# 2Axis-5_0-_-_0522.net
KiCad netlist of a schematic drawn in EasyEDA Pro
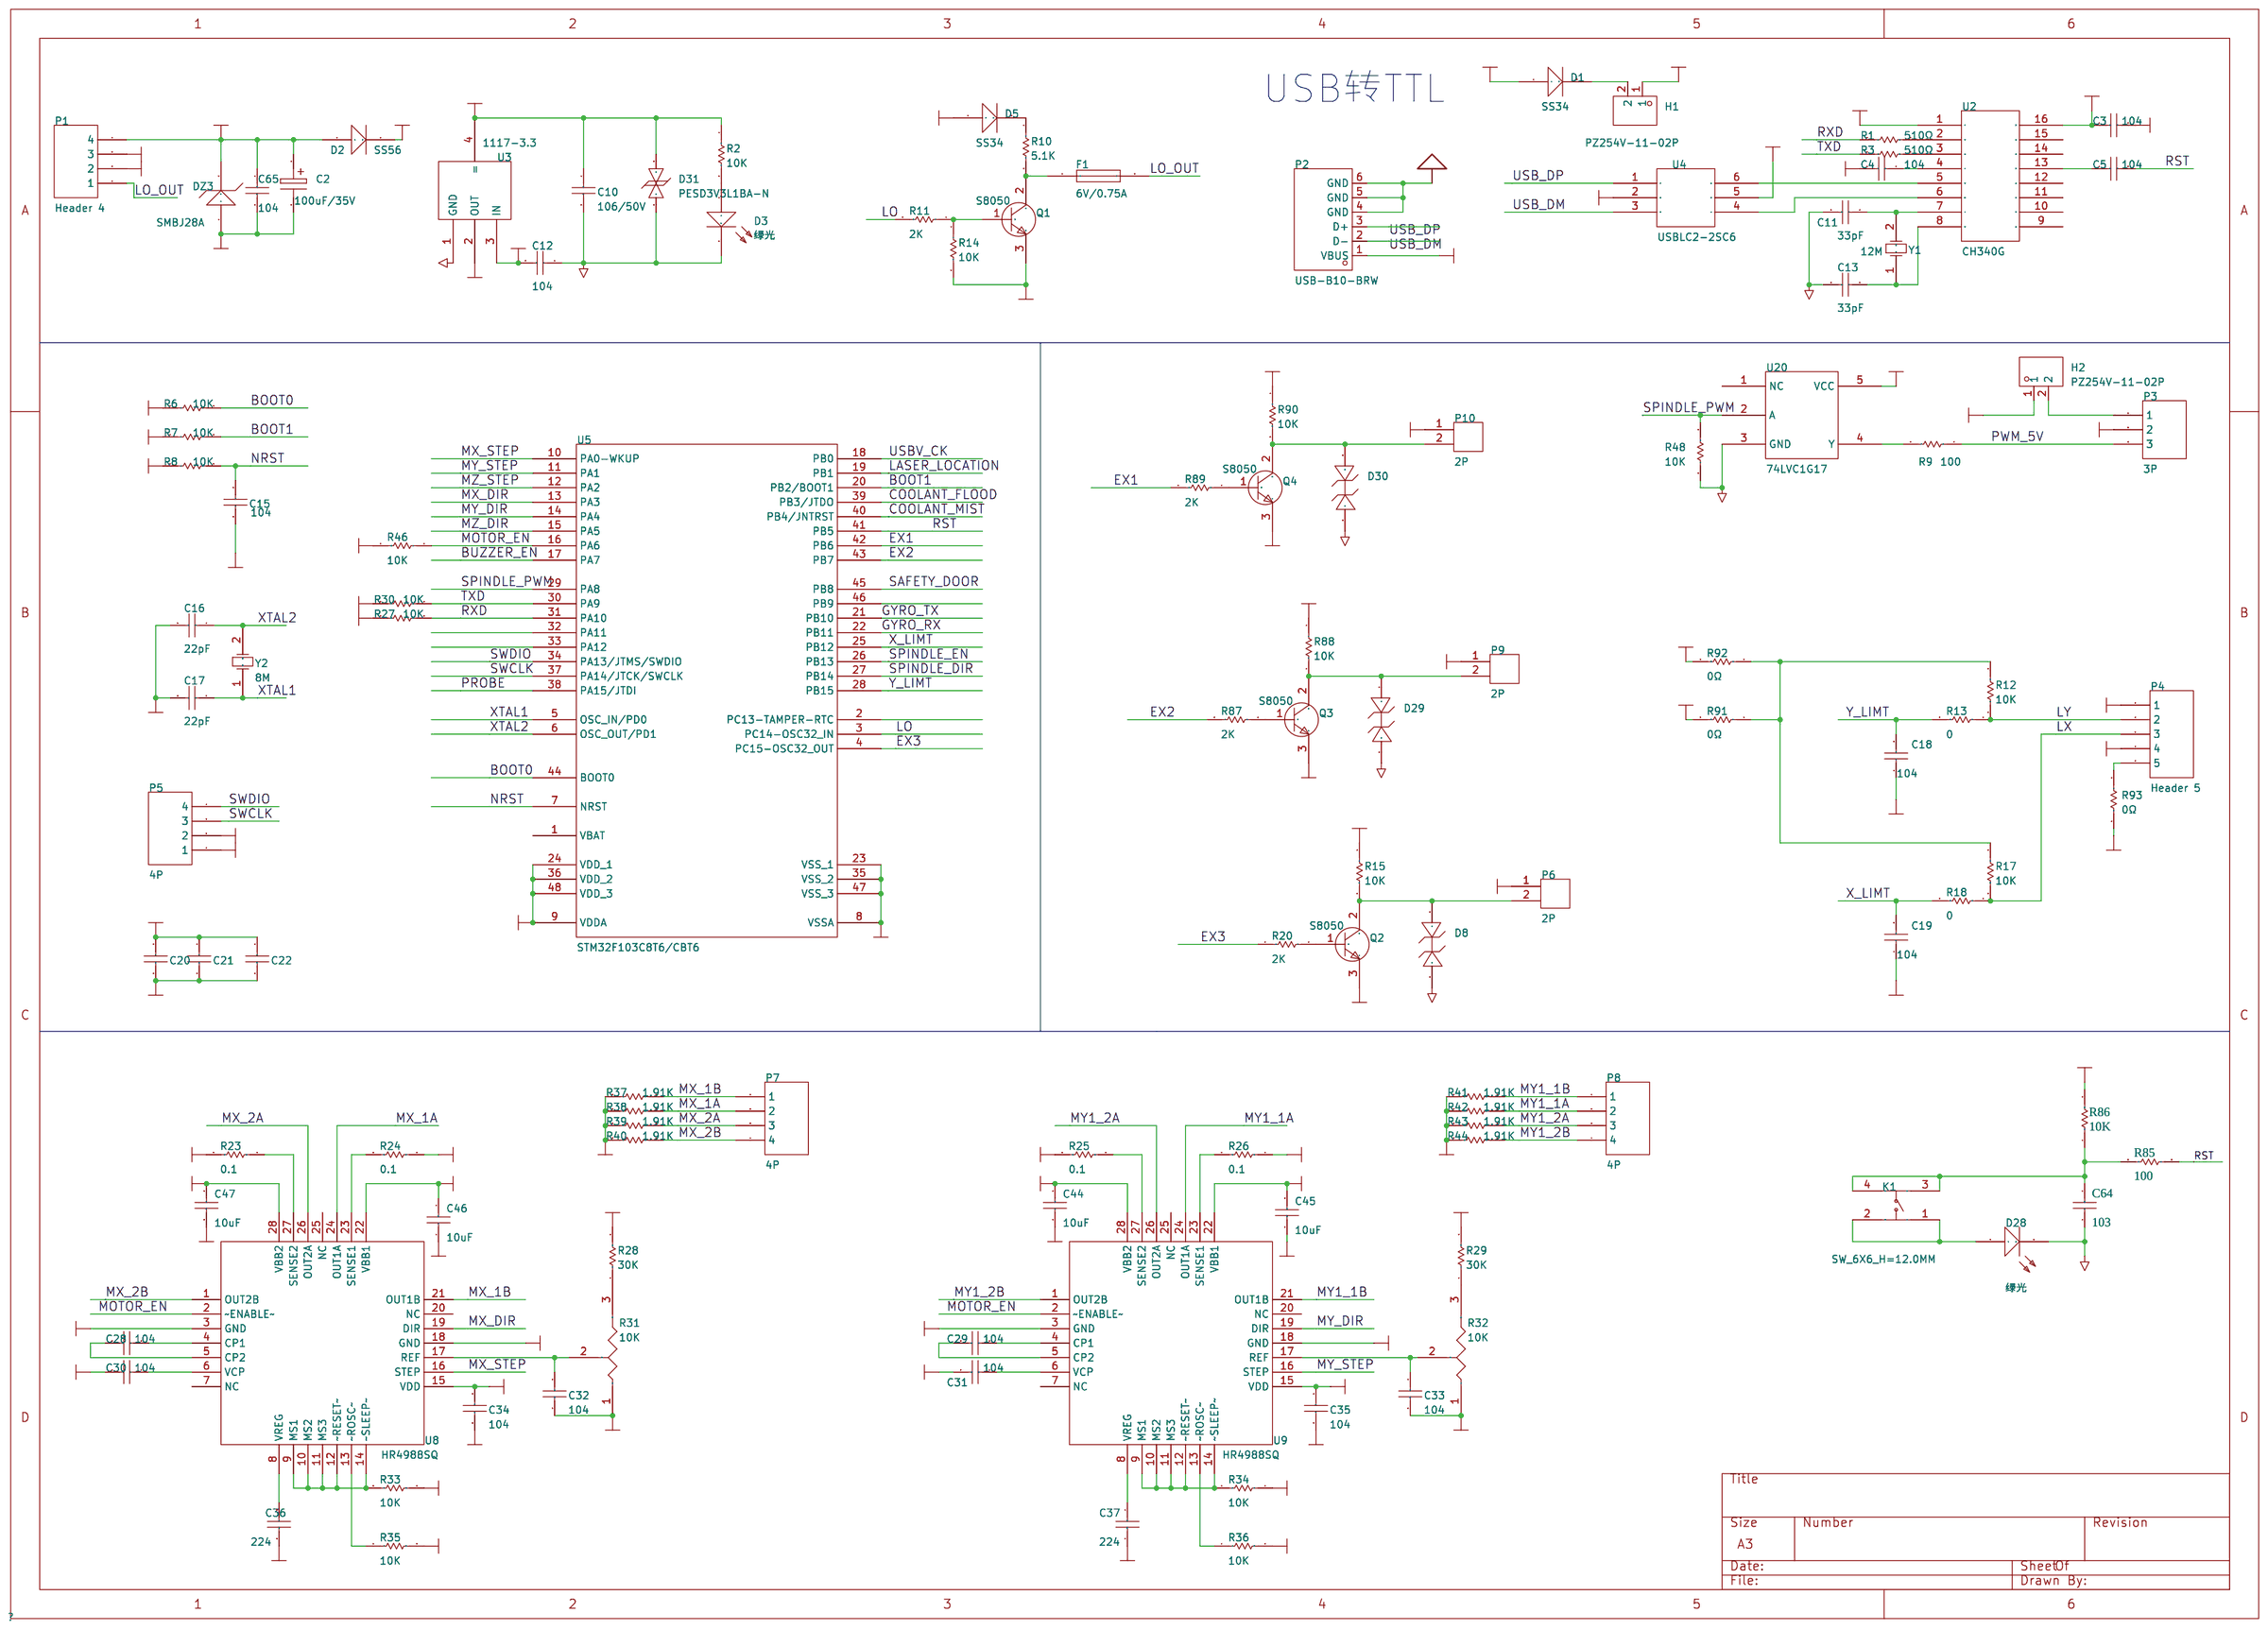
[diagram p0: 2轴南塘]
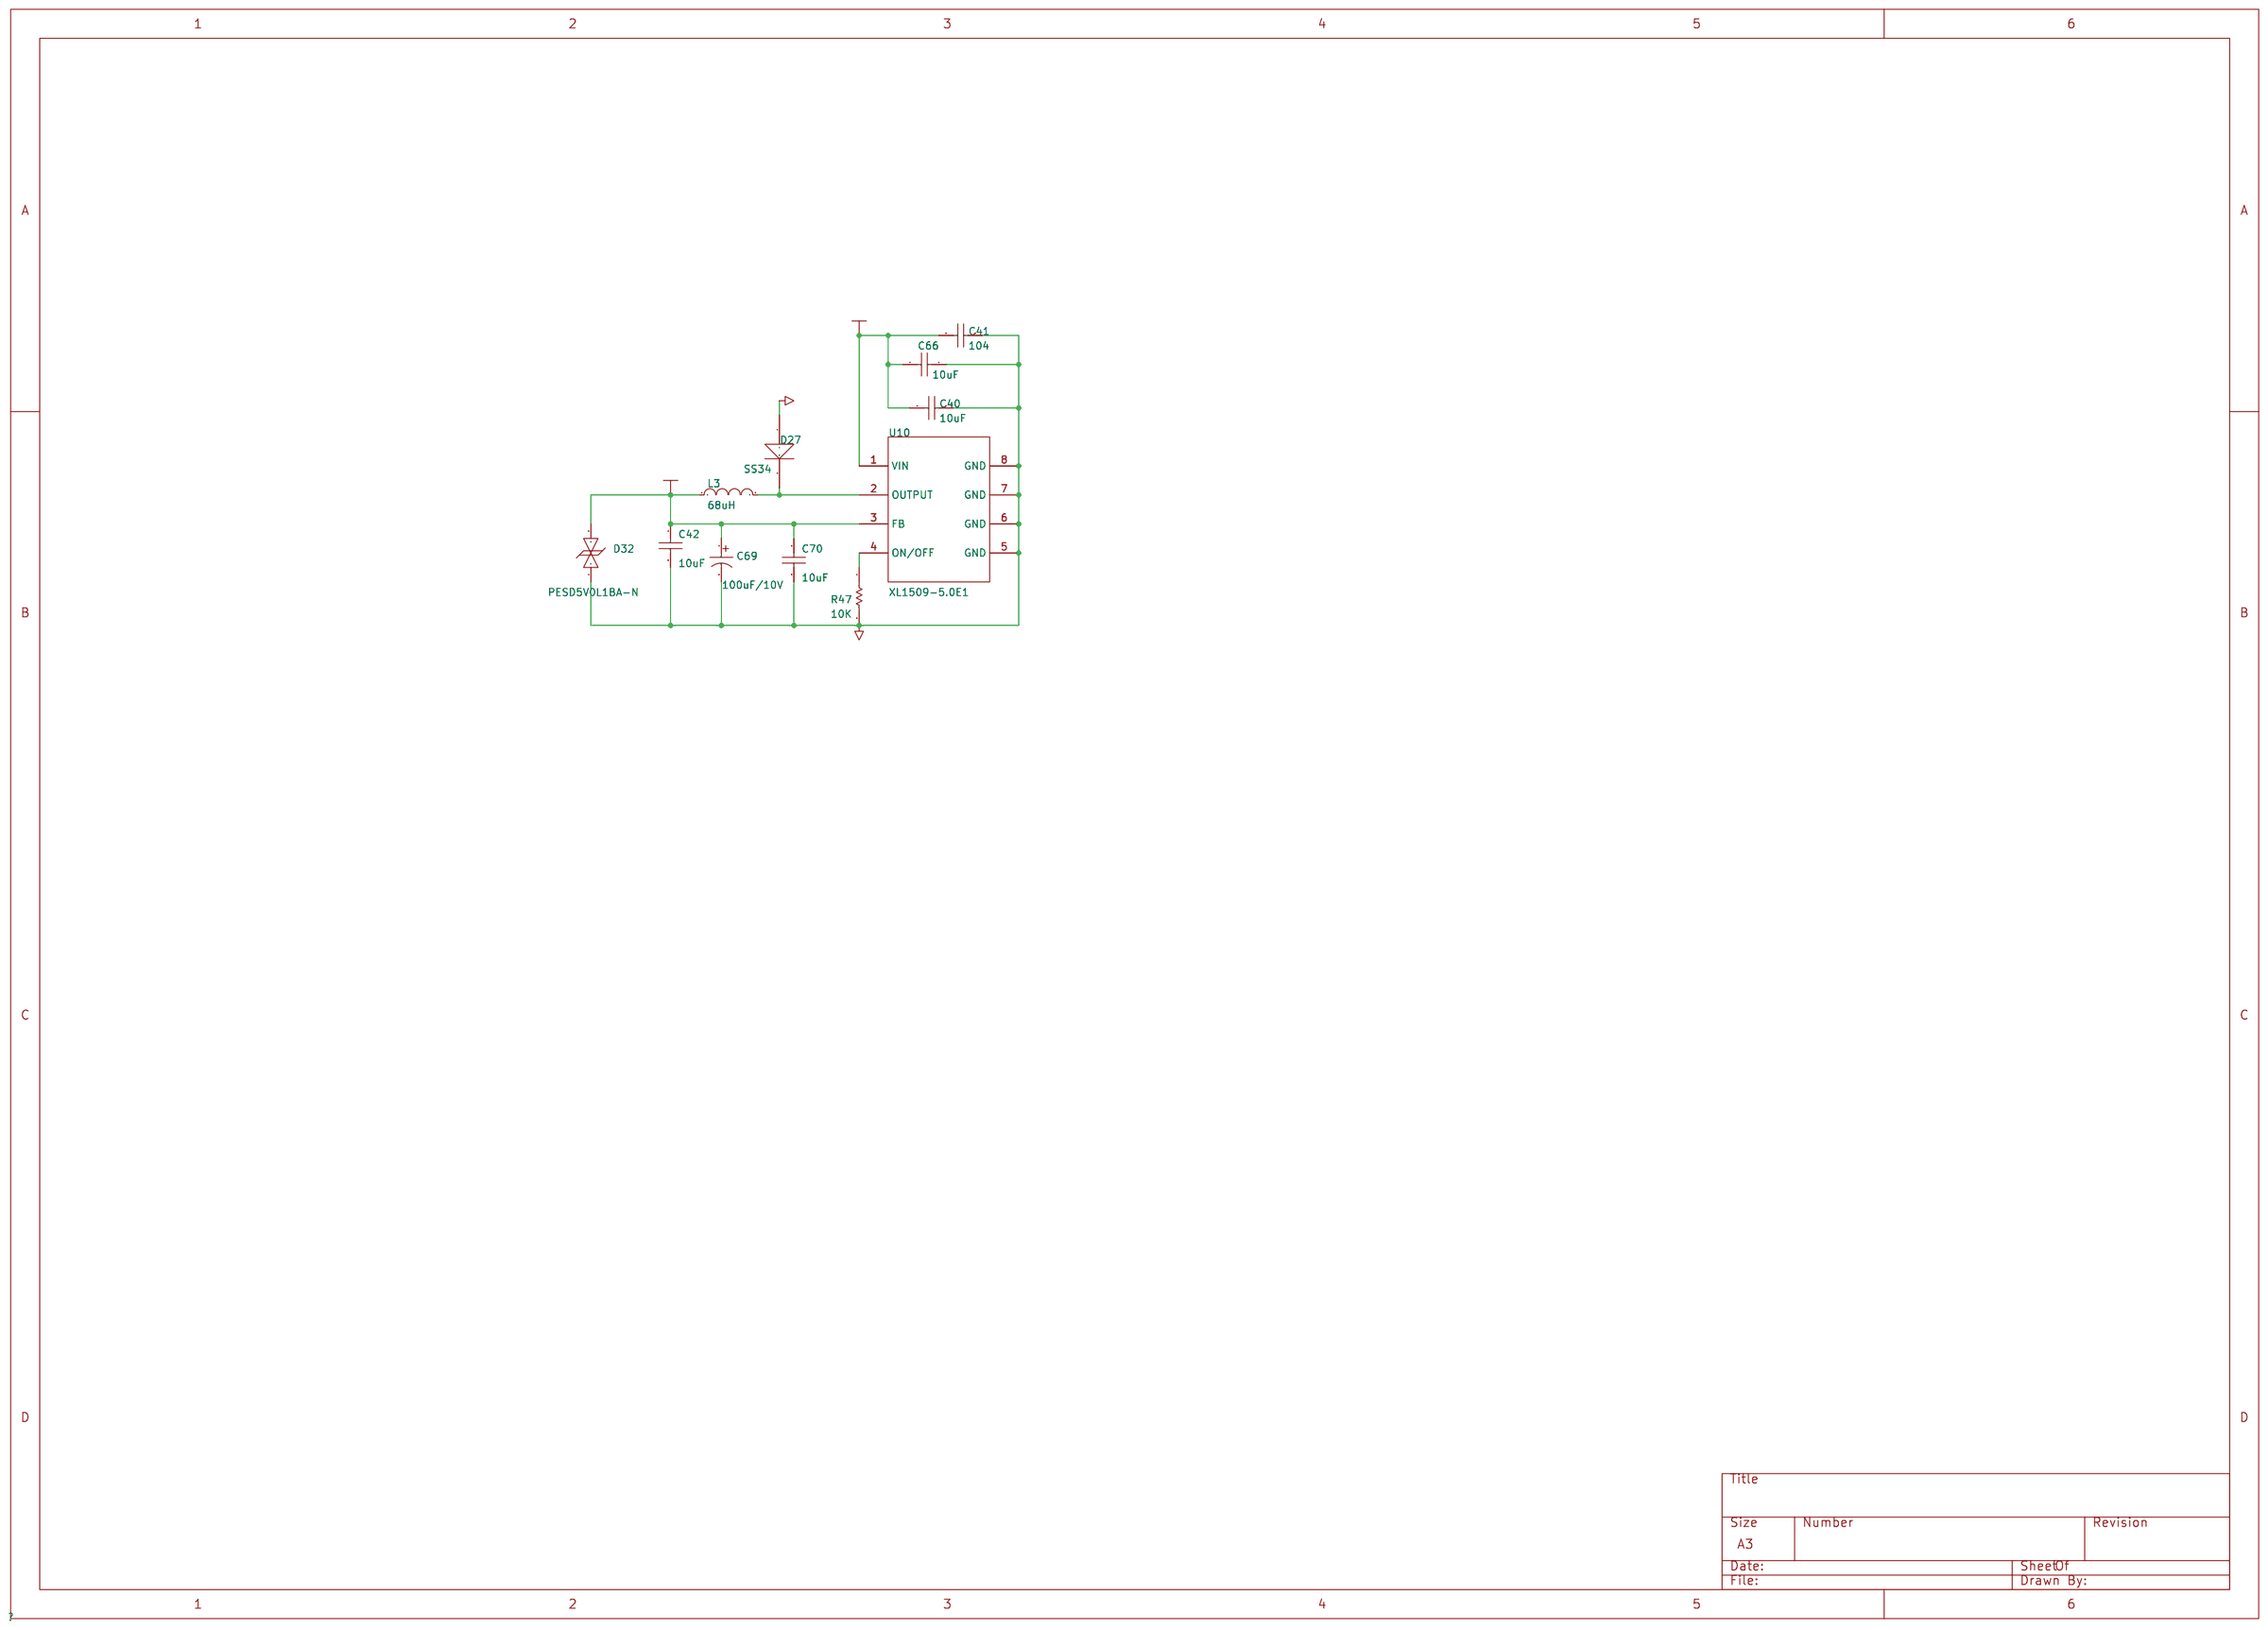
[diagram p1: 电源]

(export (version "E")
  (design (tool "Eeschema 10.0.6"))
  (components
    (comp (ref "C2")
      (value "100uF/35V")
      (footprint "easyedapro:0603C")
      (libsource (lib "easyedapro") (part "ELECTRO1"))
    )
    (comp (ref "C3")
      (value "104")
      (footprint "easyedapro:0603C")
      (description "Capacitor (Semiconductor SIM Model)")
      (libsource (lib "easyedapro") (part "Cap Semi"))
    )
    (comp (ref "C4")
      (value "104")
      (footprint "easyedapro:0603C")
      (description "Capacitor (Semiconductor SIM Model)")
      (libsource (lib "easyedapro") (part "Cap Semi"))
    )
    (comp (ref "C5")
      (value "104")
      (footprint "easyedapro:0603C")
      (description "Capacitor (Semiconductor SIM Model)")
      (libsource (lib "easyedapro") (part "Cap Semi"))
    )
    (comp (ref "C10")
      (value "106/50V")
      (footprint "easyedapro:0603C")
      (description "Capacitor (Semiconductor SIM Model)")
      (libsource (lib "easyedapro") (part "Cap Semi"))
    )
    (comp (ref "C11")
      (value "18pF")
      (footprint "easyedapro:0603C")
      (description "Capacitor (Semiconductor SIM Model)")
      (libsource (lib "easyedapro") (part "Cap Semi"))
    )
    (comp (ref "C12")
      (value "104")
      (footprint "easyedapro:0603C")
      (description "Capacitor (Semiconductor SIM Model)")
      (libsource (lib "easyedapro") (part "Cap Semi"))
    )
    (comp (ref "C13")
      (value "18pF")
      (footprint "easyedapro:0603C")
      (description "Capacitor (Semiconductor SIM Model)")
      (libsource (lib "easyedapro") (part "Cap Semi"))
    )
    (comp (ref "C15")
      (value "104")
      (footprint "easyedapro:0603C")
      (description "Capacitor (Semiconductor SIM Model)")
      (libsource (lib "easyedapro") (part "Cap Semi"))
    )
    (comp (ref "C16")
      (value "100pF")
      (footprint "easyedapro:0603C")
      (description "Capacitor (Semiconductor SIM Model)")
      (libsource (lib "easyedapro") (part "Cap Semi"))
    )
    (comp (ref "C17")
      (value "100pF")
      (footprint "easyedapro:0603C")
      (description "Capacitor (Semiconductor SIM Model)")
      (libsource (lib "easyedapro") (part "Cap Semi"))
    )
    (comp (ref "C18") (value "104") (footprint "easyedapro:0603C") (libsource (lib "") (part "CAP_1")))
    (comp (ref "C19") (value "104") (footprint "easyedapro:0603C") (libsource (lib "") (part "CAP_1")))
    (comp (ref "C20") (value "104") (footprint "easyedapro:0603C") (libsource (lib "") (part "CAP_1")))
    (comp (ref "C21") (value "104") (footprint "easyedapro:0603C") (libsource (lib "") (part "CAP_1")))
    (comp (ref "C22") (value "104") (footprint "easyedapro:0603C") (libsource (lib "") (part "CAP_1")))
    (comp (ref "C28") (value "104") (footprint "easyedapro:0603C") (libsource (lib "") (part "CAP_1")))
    (comp (ref "C29") (value "104") (footprint "easyedapro:0603C") (libsource (lib "") (part "CAP_1")))
    (comp (ref "C30") (value "104") (footprint "easyedapro:0603C") (libsource (lib "") (part "CAP_1")))
    (comp (ref "C31") (value "104") (footprint "easyedapro:0603C") (libsource (lib "") (part "CAP_1")))
    (comp (ref "C32") (value "104") (footprint "easyedapro:0603C") (libsource (lib "") (part "CAP_1")))
    (comp (ref "C33") (value "104") (footprint "easyedapro:0603C") (libsource (lib "") (part "CAP_1")))
    (comp (ref "C34") (value "104") (footprint "easyedapro:0603C") (libsource (lib "") (part "CAP_1")))
    (comp (ref "C35") (value "104") (footprint "easyedapro:0603C") (libsource (lib "") (part "CAP_1")))
    (comp (ref "C36") (value "224") (footprint "easyedapro:0603C") (libsource (lib "") (part "CAP_1")))
    (comp (ref "C37") (value "224") (footprint "easyedapro:0603C") (libsource (lib "") (part "CAP_1")))
    (comp (ref "C44") (value "10uF") (libsource (lib "easyedapro") (part "CAP")))
    (comp (ref "C45") (value "10uF") (libsource (lib "easyedapro") (part "CAP")))
    (comp (ref "C46") (value "10uF") (libsource (lib "easyedapro") (part "CAP")))
    (comp (ref "C47") (value "10uF") (libsource (lib "easyedapro") (part "CAP")))
    (comp (ref "C64") (value "103") (libsource (lib "easyedapro") (part "CAP")))
    (comp (ref "C65")
      (value "104")
      (footprint "easyedapro:0603C")
      (description "Capacitor (Semiconductor SIM Model)")
      (libsource (lib "easyedapro") (part "Cap Semi"))
    )
    (comp (ref "D1")
      (value "SS34")
      (footprint "easyedapro:SMA")
      (libsource (lib "easyedapro") (part "1N4148"))
    )
    (comp (ref "D2")
      (value "SS56")
      (footprint "easyedapro:SMA")
      (libsource (lib "easyedapro") (part "1N4148"))
    )
    (comp (ref "D3")
      (value "绿光")
      (footprint "easyedapro:0603LED")
      (libsource (lib "easyedapro") (part "LED"))
    )
    (comp (ref "D5")
      (value "SS34")
      (footprint "easyedapro:SMA")
      (libsource (lib "easyedapro") (part "1N4148"))
    )
    (comp (ref "D8")
      (value "ESD05V52D-C")
      (fields (field (name "Manufacturer") "TWGMC(台湾迪嘉)"))
      (libsource (lib "easyedapro") (part "ESD05V52D-C"))
    )
    (comp (ref "D28")
      (value "绿光")
      (footprint "easyedapro:0603LED")
      (libsource (lib "easyedapro") (part "LED"))
    )
    (comp (ref "D29")
      (value "ESD05V52D-C")
      (fields (field (name "Manufacturer") "TWGMC(台湾迪嘉)"))
      (libsource (lib "easyedapro") (part "ESD05V52D-C"))
    )
    (comp (ref "D30")
      (value "ESD05V52D-C")
      (fields (field (name "Manufacturer") "TWGMC(台湾迪嘉)"))
      (libsource (lib "easyedapro") (part "ESD05V52D-C"))
    )
    (comp (ref "D31")
      (value "PESD3V3L1BA-N")
      (footprint "easyedapro:SOD-523_L1.2-W0.8-LS1.6-BI")
      (description "极性:Bidirectional;反向关断电压（典型值）:5V (Max);击穿电压（最小值）:6V;箝位电压:15V;峰值脉冲电流（10/1000us）:5A (8/20us);")
      (fields (field (name "Manufacturer") "BORN伯恩半导体"))
      (libsource (lib "easyedapro") (part "PESD5V0S1BBN"))
    )
    (comp (ref "DZ3")
      (value "SMBJ28A")
      (footprint "easyedapro:SMA")
      (libsource (lib "easyedapro") (part "稳压二极管"))
    )
    (comp (ref "F1")
      (value "6V/0.75A")
      (footprint "easyedapro:1206R")
      (description "保险丝")
      (libsource (lib "easyedapro") (part "FUSE1"))
    )
    (comp (ref "H1")
      (value "PZ254V-11-02P")
      (footprint "easyedapro:HDR-TH_2P-P2.54-V-M")
      (fields (field (name "Manufacturer") "XFCN(兴飞)"))
      (libsource (lib "easyedapro") (part "PZ254V-11-02P"))
    )
    (comp (ref "H2")
      (value "PZ254V-11-02P")
      (footprint "easyedapro:HDR-TH_2P-P2.54-V-M")
      (fields (field (name "Manufacturer") "XFCN(兴飞)"))
      (libsource (lib "easyedapro") (part "PZ254V-11-02P"))
    )
    (comp (ref "K1")
      (value "SW_6X6_H=12.0MM")
      (footprint "easyedapro:KEY-SMD_4P-L6.0-W6.0-P4.50-LS9.0")
      (libsource (lib "easyedapro") (part "SW_6X6_H=12.0MM"))
    )
    (comp (ref "P1")
      (value "Header 4")
      (footprint "easyedapro:VH3.96-4P直插座")
      (description "Header, 4-Pin")
      (libsource (lib "easyedapro") (part "Header 4"))
    )
    (comp (ref "P2")
      (value "USB-B10-BRW")
      (footprint "easyedapro:USB-B-TH_USB-B10-BRW")
      (fields (field (name "Manufacturer") "XUNPU(讯普)"))
      (libsource (lib "easyedapro") (part "USB-B10-BRW"))
    )
    (comp (ref "P3")
      (value "3P")
      (footprint "easyedapro:HDR1X3_CON")
      (libsource (lib "easyedapro") (part "3P"))
    )
    (comp (ref "P4")
      (value "Header 5")
      (footprint "easyedapro:HDR1X5_CON")
      (description "Header, 5-Pin")
      (libsource (lib "easyedapro") (part "Header 5"))
    )
    (comp (ref "P5") (value "4P") (footprint "easyedapro:SIP4") (libsource (lib "easyedapro") (part "4P")))
    (comp (ref "P6")
      (value "2P")
      (footprint "easyedapro:HDR1X2_CON")
      (libsource (lib "easyedapro") (part "2P"))
    )
    (comp (ref "P7") (value "4P") (footprint "easyedapro:SIP4") (libsource (lib "easyedapro") (part "4P")))
    (comp (ref "P8") (value "4P") (footprint "easyedapro:SIP4") (libsource (lib "easyedapro") (part "4P")))
    (comp (ref "P9")
      (value "2P")
      (footprint "easyedapro:HDR1X2_CON")
      (libsource (lib "easyedapro") (part "2P"))
    )
    (comp (ref "P10")
      (value "2P")
      (footprint "easyedapro:HDR1X2_CON")
      (libsource (lib "easyedapro") (part "2P"))
    )
    (comp (ref "Q1")
      (value "S8050")
      (footprint "easyedapro:SOT-23")
      (libsource (lib "easyedapro") (part "NPN"))
    )
    (comp (ref "Q2")
      (value "S8050")
      (footprint "easyedapro:SOT-23")
      (libsource (lib "easyedapro") (part "NPN"))
    )
    (comp (ref "Q3")
      (value "S8050")
      (footprint "easyedapro:SOT-23")
      (libsource (lib "easyedapro") (part "NPN"))
    )
    (comp (ref "Q4")
      (value "S8050")
      (footprint "easyedapro:SOT-23")
      (libsource (lib "easyedapro") (part "NPN"))
    )
    (comp (ref "R1")
      (value "510Ω")
      (footprint "easyedapro:1206R")
      (description "Resistor")
      (libsource (lib "") (part "RES_1"))
    )
    (comp (ref "R2")
      (value "10K")
      (footprint "easyedapro:1206R")
      (description "Resistor")
      (libsource (lib "") (part "RES_1"))
    )
    (comp (ref "R3")
      (value "510Ω")
      (footprint "easyedapro:1206R")
      (description "Resistor")
      (libsource (lib "") (part "RES_1"))
    )
    (comp (ref "R6")
      (value "10K")
      (footprint "easyedapro:1206R")
      (description "Resistor")
      (libsource (lib "") (part "RES_1"))
    )
    (comp (ref "R7")
      (value "10K")
      (footprint "easyedapro:1206R")
      (description "Resistor")
      (libsource (lib "") (part "RES_1"))
    )
    (comp (ref "R8")
      (value "10K")
      (footprint "easyedapro:1206R")
      (description "Resistor")
      (libsource (lib "") (part "RES_1"))
    )
    (comp (ref "R9")
      (value "100")
      (footprint "easyedapro:1206R")
      (description "Resistor")
      (libsource (lib "") (part "RES_1"))
    )
    (comp (ref "R10")
      (value "5.1K")
      (footprint "easyedapro:1206R")
      (description "Resistor")
      (libsource (lib "") (part "RES_1"))
    )
    (comp (ref "R11")
      (value "2K")
      (footprint "easyedapro:1206R")
      (description "Resistor")
      (libsource (lib "") (part "RES_1"))
    )
    (comp (ref "R12")
      (value "10K")
      (footprint "easyedapro:1206R")
      (description "Resistor")
      (libsource (lib "") (part "RES_1"))
    )
    (comp (ref "R13")
      (value "0")
      (footprint "easyedapro:1206R")
      (description "Resistor")
      (libsource (lib "") (part "RES_1"))
    )
    (comp (ref "R14")
      (value "10K")
      (footprint "easyedapro:1206R")
      (description "Resistor")
      (libsource (lib "") (part "RES_1"))
    )
    (comp (ref "R15")
      (value "10K")
      (footprint "easyedapro:1206R")
      (description "Resistor")
      (libsource (lib "") (part "RES_1"))
    )
    (comp (ref "R17")
      (value "10K")
      (footprint "easyedapro:1206R")
      (description "Resistor")
      (libsource (lib "") (part "RES_1"))
    )
    (comp (ref "R18")
      (value "0")
      (footprint "easyedapro:1206R")
      (description "Resistor")
      (libsource (lib "") (part "RES_1"))
    )
    (comp (ref "R20")
      (value "2K")
      (footprint "easyedapro:1206R")
      (description "Resistor")
      (libsource (lib "") (part "RES_1"))
    )
    (comp (ref "R23")
      (value "0.1")
      (footprint "easyedapro:1206R")
      (description "Resistor")
      (libsource (lib "") (part "RES_1"))
    )
    (comp (ref "R24")
      (value "0.1")
      (footprint "easyedapro:1206R")
      (description "Resistor")
      (libsource (lib "") (part "RES_1"))
    )
    (comp (ref "R25")
      (value "0.1")
      (footprint "easyedapro:1206R")
      (description "Resistor")
      (libsource (lib "") (part "RES_1"))
    )
    (comp (ref "R26")
      (value "0.1")
      (footprint "easyedapro:1206R")
      (description "Resistor")
      (libsource (lib "") (part "RES_1"))
    )
    (comp (ref "R27")
      (value "10K")
      (footprint "easyedapro:1206R")
      (description "Resistor")
      (libsource (lib "") (part "RES_1"))
    )
    (comp (ref "R28")
      (value "10K")
      (footprint "easyedapro:1206R")
      (description "Resistor")
      (libsource (lib "") (part "RES_1"))
    )
    (comp (ref "R29")
      (value "10K")
      (footprint "easyedapro:1206R")
      (description "Resistor")
      (libsource (lib "") (part "RES_1"))
    )
    (comp (ref "R30")
      (value "10K")
      (footprint "easyedapro:1206R")
      (description "Resistor")
      (libsource (lib "") (part "RES_1"))
    )
    (comp (ref "R31")
      (value "10K")
      (footprint "easyedapro:松下贴片电位器3x3")
      (libsource (lib "easyedapro") (part "电位器"))
    )
    (comp (ref "R32")
      (value "10K")
      (footprint "easyedapro:松下贴片电位器3x3")
      (libsource (lib "easyedapro") (part "电位器"))
    )
    (comp (ref "R33")
      (value "10K")
      (footprint "easyedapro:1206R")
      (description "Resistor")
      (libsource (lib "") (part "RES_1"))
    )
    (comp (ref "R34")
      (value "10K")
      (footprint "easyedapro:1206R")
      (description "Resistor")
      (libsource (lib "") (part "RES_1"))
    )
    (comp (ref "R35")
      (value "10K")
      (footprint "easyedapro:1206R")
      (description "Resistor")
      (libsource (lib "") (part "RES_1"))
    )
    (comp (ref "R36")
      (value "10K")
      (footprint "easyedapro:1206R")
      (description "Resistor")
      (libsource (lib "") (part "RES_1"))
    )
    (comp (ref "R37")
      (value "1.91K")
      (footprint "easyedapro:1206R")
      (description "Resistor")
      (libsource (lib "") (part "RES_1"))
    )
    (comp (ref "R38")
      (value "1.91K")
      (footprint "easyedapro:1206R")
      (description "Resistor")
      (libsource (lib "") (part "RES_1"))
    )
    (comp (ref "R39")
      (value "1.91K")
      (footprint "easyedapro:1206R")
      (description "Resistor")
      (libsource (lib "") (part "RES_1"))
    )
    (comp (ref "R40")
      (value "1.91K")
      (footprint "easyedapro:1206R")
      (description "Resistor")
      (libsource (lib "") (part "RES_1"))
    )
    (comp (ref "R41")
      (value "1.91K")
      (footprint "easyedapro:1206R")
      (description "Resistor")
      (libsource (lib "") (part "RES_1"))
    )
    (comp (ref "R42")
      (value "1.91K")
      (footprint "easyedapro:1206R")
      (description "Resistor")
      (libsource (lib "") (part "RES_1"))
    )
    (comp (ref "R43")
      (value "1.91K")
      (footprint "easyedapro:1206R")
      (description "Resistor")
      (libsource (lib "") (part "RES_1"))
    )
    (comp (ref "R44")
      (value "1.91K")
      (footprint "easyedapro:1206R")
      (description "Resistor")
      (libsource (lib "") (part "RES_1"))
    )
    (comp (ref "R46")
      (value "10K")
      (footprint "easyedapro:1206R")
      (description "Resistor")
      (libsource (lib "") (part "RES_1"))
    )
    (comp (ref "R48")
      (value "10K")
      (description "Resistor")
      (fields (field (name "Publisher") "Altium Limited"))
      (libsource (lib "easyedapro") (part "RES"))
    )
    (comp (ref "R85")
      (value "100")
      (description "Resistor")
      (fields (field (name "Publisher") "Altium Limited"))
      (libsource (lib "easyedapro") (part "RES"))
    )
    (comp (ref "R86")
      (value "10K")
      (description "Resistor")
      (fields (field (name "Publisher") "Altium Limited"))
      (libsource (lib "easyedapro") (part "RES"))
    )
    (comp (ref "R87")
      (value "2K")
      (footprint "easyedapro:1206R")
      (description "Resistor")
      (libsource (lib "") (part "RES_1"))
    )
    (comp (ref "R88")
      (value "10K")
      (footprint "easyedapro:1206R")
      (description "Resistor")
      (libsource (lib "") (part "RES_1"))
    )
    (comp (ref "R89")
      (value "2K")
      (footprint "easyedapro:1206R")
      (description "Resistor")
      (libsource (lib "") (part "RES_1"))
    )
    (comp (ref "R90")
      (value "10K")
      (footprint "easyedapro:1206R")
      (description "Resistor")
      (libsource (lib "") (part "RES_1"))
    )
    (comp (ref "R91")
      (value "0Ω")
      (footprint "easyedapro:1206R")
      (description "Resistor")
      (libsource (lib "") (part "RES_1"))
    )
    (comp (ref "R92")
      (value "0Ω")
      (footprint "easyedapro:1206R")
      (description "Resistor")
      (libsource (lib "") (part "RES_1"))
    )
    (comp (ref "R93")
      (value "0Ω")
      (footprint "easyedapro:1206R")
      (description "Resistor")
      (libsource (lib "") (part "RES_1"))
    )
    (comp (ref "U2")
      (value "CH340G")
      (footprint "easyedapro:SOP16")
      (libsource (lib "easyedapro") (part "DIP16"))
    )
    (comp (ref "U3")
      (value "1117-3.3")
      (footprint "easyedapro:SOT-223")
      (libsource (lib "easyedapro") (part "LM1117"))
    )
    (comp (ref "U4")
      (value "USBLC2-2SC6")
      (footprint "easyedapro:SOT-23-6")
      (libsource (lib "easyedapro") (part "DIP6"))
    )
    (comp (ref "U5")
      (value "STM32F103C8T6/CBT6")
      (footprint "easyedapro:LQFP48")
      (description "STM32 ARM-based 32-bit MCU with 32 Kbytes Flash, 48-pin LQFP, Industrial Temperature")
      (libsource (lib "easyedapro") (part "STM32F103C6T6"))
    )
    (comp (ref "U8")
      (value "HR4988SQ")
      (footprint "easyedapro:QFN28")
      (libsource (lib "easyedapro") (part "HR4988"))
    )
    (comp (ref "U9")
      (value "HR4988SQ")
      (footprint "easyedapro:QFN28")
      (libsource (lib "easyedapro") (part "HR4988"))
    )
    (comp (ref "U20")
      (value "74LVC1G17")
      (footprint "easyedapro:SMD8")
      (libsource (lib "easyedapro") (part "74LVC1G04"))
    )
    (comp (ref "Y1")
      (value "12M")
      (footprint "easyedapro:晶振贴片49SSMD")
      (description "Crystal Oscillator")
      (libsource (lib "easyedapro") (part "XTAL"))
    )
    (comp (ref "Y2")
      (value "8M")
      (footprint "easyedapro:晶振贴片49SSMD")
      (description "Crystal Oscillator")
      (libsource (lib "easyedapro") (part "XTAL"))
    )
    (comp (ref "C40") (value "10uF") (libsource (lib "easyedapro") (part "CAP")))
    (comp (ref "C41")
      (value "104")
      (footprint "easyedapro:0603C")
      (description "Capacitor (Semiconductor SIM Model)")
      (libsource (lib "easyedapro") (part "Cap Semi"))
    )
    (comp (ref "C42") (value "10uF") (libsource (lib "easyedapro") (part "CAP")))
    (comp (ref "C66") (value "10uF") (libsource (lib "easyedapro") (part "CAP")))
    (comp (ref "C69")
      (value "100uF/10V")
      (footprint "easyedapro:CAP-SMD_BD5.0-L5.3-W5.3-RD")
      (fields (field (name "Manufacturer Part") "CS1A101M-CRD54") (field (name "Manufacturer") "ST(先科)"))
      (libsource (lib "easyedapro") (part "CS1A101M-CRD54"))
    )
    (comp (ref "C70") (value "10uF") (libsource (lib "easyedapro") (part "CAP")))
    (comp (ref "D27") (value "SS34") (libsource (lib "easyedapro") (part "1N4148")))
    (comp (ref "D32")
      (value "PESD5V0L1BA-N")
      (footprint "easyedapro:SOD-523_L1.2-W0.8-LS1.6-BI")
      (description "极性:Bidirectional;反向关断电压（典型值）:5V (Max);击穿电压（最小值）:6V;箝位电压:15V;峰值脉冲电流（10/1000us）:5A (8/20us);")
      (fields (field (name "Manufacturer") "BORN伯恩半导体"))
      (libsource (lib "easyedapro") (part "PESD5V0S1BBN"))
    )
    (comp (ref "L3")
      (value "68uH")
      (footprint "easyedapro:IND-SMD_L7.0-W7.0_SMDRI74-330MT")
      (description "电感值:33uH;精度:±20%;额定电流:960mA;饱和电流(Isat):1.8A;类型:屏蔽电感;")
      (fields (field (name "Manufacturer Part") "SMDRI74-330MT") (field (name "Manufacturer") "SXN(顺翔诺)"))
      (libsource (lib "easyedapro") (part "SMDRI74-330MT"))
    )
    (comp (ref "R47")
      (value "10K")
      (footprint "easyedapro:1206R")
      (description "Resistor")
      (libsource (lib "easyedapro") (part "RES"))
    )
    (comp (ref "U10")
      (value "XL1509-5.0E1")
      (footprint "easyedapro:SOIC-8_L5.0-W4.0-P1.27-LS6.0-BL")
      (description "功能类型:降压型;同步整流:-;输出通道数:-;拓扑结构:-;输入电压:-;输出电流(最大值):-;开关频率:-;")
      (fields (field (name "Manufacturer") "XLSEMI(芯龙)"))
      (libsource (lib "easyedapro") (part "XL1509-5.0E1"))
    )
  )
  (nets
    (net (code "1") (name "3V3") (class "Default")
      (node (ref "C10") (pin "1") (pinfunction "1_1") (pintype "unspecified"))
      (node (ref "C20") (pin "2") (pinfunction "2_2") (pintype "unspecified"))
      (node (ref "C21") (pin "2") (pinfunction "2_2") (pintype "unspecified"))
      (node (ref "C22") (pin "2") (pinfunction "2_2") (pintype "unspecified"))
      (node (ref "D31") (pin "2") (pinfunction "2_2") (pintype "input"))
      (node (ref "P5") (pin "2") (pinfunction "2_2") (pintype "unspecified"))
      (node (ref "R2") (pin "1") (pinfunction "1_1") (pintype "unspecified"))
      (node (ref "R27") (pin "1") (pinfunction "1_1") (pintype "unspecified"))
      (node (ref "R30") (pin "1") (pinfunction "1_1") (pintype "unspecified"))
      (node (ref "R46") (pin "2") (pinfunction "2_2") (pintype "unspecified"))
      (node (ref "R8") (pin "1") (pinfunction "1_1") (pintype "unspecified"))
      (node (ref "R86") (pin "2") (pinfunction "2_2") (pintype "input"))
      (node (ref "R92") (pin "2") (pinfunction "2_2") (pintype "unspecified"))
      (node (ref "U3") (pin "2") (pinfunction "OUT_2") (pintype "unspecified"))
      (node (ref "U3") (pin "4") (pinfunction "=_4") (pintype "unspecified"))
      (node (ref "U5") (pin "24") (pinfunction "VDD_1_24") (pintype "unspecified"))
      (node (ref "U5") (pin "36") (pinfunction "VDD_2_36") (pintype "unspecified"))
      (node (ref "U5") (pin "48") (pinfunction "VDD_3_48") (pintype "unspecified"))
      (node (ref "U5") (pin "9") (pinfunction "VDDA_9") (pintype "unspecified"))
    )
    (net (code "2") (name "5VV") (class "Default")
      (node (ref "P1") (pin "2") (pinfunction "2_2") (pintype "unspecified"))
    )
    (net (code "3") (name "24V") (class "Default")
      (node (ref "C40") (pin "2") (pinfunction "2_2") (pintype "input"))
      (node (ref "C41") (pin "2") (pinfunction "2_2") (pintype "unspecified"))
      (node (ref "C66") (pin "1") (pinfunction "1_1") (pintype "input"))
      (node (ref "D2") (pin "2") (pinfunction "2_2") (pintype "unspecified"))
      (node (ref "H2") (pin "1") (pinfunction "1_1") (pintype "unspecified"))
      (node (ref "U10") (pin "1") (pinfunction "VIN_1") (pintype "input"))
    )
    (net (code "4") (name "BOOT0") (class "Default")
      (node (ref "R6") (pin "2") (pinfunction "2_2") (pintype "unspecified"))
      (node (ref "U5") (pin "44") (pinfunction "BOOT0_44") (pintype "input"))
    )
    (net (code "5") (name "BOOT1") (class "Default")
      (node (ref "R7") (pin "2") (pinfunction "2_2") (pintype "unspecified"))
      (node (ref "U5") (pin "20") (pinfunction "PB2/BOOT1_20") (pintype "bidirectional"))
    )
    (net (code "6") (name "BUZZER_EN") (class "Default")
      (node (ref "U5") (pin "17") (pinfunction "PA7_17") (pintype "bidirectional"))
    )
    (net (code "7") (name "COOLANT_FLOOD") (class "Default")
      (node (ref "U5") (pin "39") (pinfunction "PB3/JTDO_39") (pintype "bidirectional"))
    )
    (net (code "8") (name "COOLANT_MIST") (class "Default")
      (node (ref "U5") (pin "40") (pinfunction "PB4/JNTRST_40") (pintype "bidirectional"))
    )
    (net (code "9") (name "EX1") (class "Default")
      (node (ref "R89") (pin "2") (pinfunction "2_2") (pintype "unspecified"))
      (node (ref "U5") (pin "42") (pinfunction "PB6_42") (pintype "bidirectional"))
    )
    (net (code "10") (name "EX2") (class "Default")
      (node (ref "R87") (pin "2") (pinfunction "2_2") (pintype "unspecified"))
      (node (ref "U5") (pin "43") (pinfunction "PB7_43") (pintype "bidirectional"))
    )
    (net (code "11") (name "EX3") (class "Default")
      (node (ref "R20") (pin "2") (pinfunction "2_2") (pintype "unspecified"))
      (node (ref "U5") (pin "4") (pinfunction "PC15-OSC32_OUT_4") (pintype "bidirectional"))
    )
    (net (code "12") (name "GND") (class "Default")
      (node (ref "C10") (pin "2") (pinfunction "2_2") (pintype "unspecified"))
      (node (ref "C11") (pin "2") (pinfunction "2_2") (pintype "unspecified"))
      (node (ref "C12") (pin "1") (pinfunction "1_1") (pintype "unspecified"))
      (node (ref "C13") (pin "2") (pinfunction "2_2") (pintype "unspecified"))
      (node (ref "C15") (pin "1") (pinfunction "1_1") (pintype "unspecified"))
      (node (ref "C16") (pin "2") (pinfunction "2_2") (pintype "unspecified"))
      (node (ref "C17") (pin "2") (pinfunction "2_2") (pintype "unspecified"))
      (node (ref "C18") (pin "1") (pinfunction "1_1") (pintype "unspecified"))
      (node (ref "C19") (pin "1") (pinfunction "1_1") (pintype "unspecified"))
      (node (ref "C2") (pin "2") (pintype "unspecified"))
      (node (ref "C20") (pin "1") (pinfunction "1_1") (pintype "unspecified"))
      (node (ref "C21") (pin "1") (pinfunction "1_1") (pintype "unspecified"))
      (node (ref "C22") (pin "1") (pinfunction "1_1") (pintype "unspecified"))
      (node (ref "C3") (pin "2") (pinfunction "2_2") (pintype "unspecified"))
      (node (ref "C32") (pin "2") (pinfunction "2_2") (pintype "unspecified"))
      (node (ref "C33") (pin "2") (pinfunction "2_2") (pintype "unspecified"))
      (node (ref "C34") (pin "2") (pinfunction "2_2") (pintype "unspecified"))
      (node (ref "C35") (pin "2") (pinfunction "2_2") (pintype "unspecified"))
      (node (ref "C36") (pin "2") (pinfunction "2_2") (pintype "unspecified"))
      (node (ref "C37") (pin "2") (pinfunction "2_2") (pintype "unspecified"))
      (node (ref "C4") (pin "2") (pinfunction "2_2") (pintype "unspecified"))
      (node (ref "C40") (pin "1") (pinfunction "1_1") (pintype "input"))
      (node (ref "C41") (pin "1") (pinfunction "1_1") (pintype "unspecified"))
      (node (ref "C42") (pin "2") (pinfunction "2_2") (pintype "input"))
      (node (ref "C44") (pin "2") (pinfunction "2_2") (pintype "input"))
      (node (ref "C45") (pin "2") (pinfunction "2_2") (pintype "input"))
      (node (ref "C46") (pin "2") (pinfunction "2_2") (pintype "input"))
      (node (ref "C47") (pin "2") (pinfunction "2_2") (pintype "input"))
      (node (ref "C64") (pin "1") (pinfunction "1_1") (pintype "input"))
      (node (ref "C65") (pin "2") (pinfunction "2_2") (pintype "unspecified"))
      (node (ref "C66") (pin "2") (pinfunction "2_2") (pintype "input"))
      (node (ref "C69") (pin "2") (pinfunction "2_2") (pintype "input"))
      (node (ref "C70") (pin "2") (pinfunction "2_2") (pintype "input"))
      (node (ref "D27") (pin "1") (pinfunction "1_1") (pintype "input"))
      (node (ref "D28") (pin "2") (pinfunction "2_2") (pintype "unspecified"))
      (node (ref "D29") (pin "1") (pinfunction "1_1") (pintype "unspecified"))
      (node (ref "D3") (pin "2") (pinfunction "2_2") (pintype "unspecified"))
      (node (ref "D30") (pin "1") (pinfunction "1_1") (pintype "unspecified"))
      (node (ref "D31") (pin "1") (pinfunction "1_1") (pintype "input"))
      (node (ref "D32") (pin "1") (pinfunction "1_1") (pintype "input"))
      (node (ref "D8") (pin "1") (pinfunction "1_1") (pintype "unspecified"))
      (node (ref "DZ3") (pin "1") (pinfunction "1_1") (pintype "unspecified"))
      (node (ref "P1") (pin "3") (pinfunction "3_3") (pintype "unspecified"))
      (node (ref "P10") (pin "1") (pintype "unspecified"))
      (node (ref "P2") (pin "4") (pinfunction "GND_4") (pintype "unspecified"))
      (node (ref "P2") (pin "5") (pinfunction "GND_5") (pintype "unspecified"))
      (node (ref "P2") (pin "6") (pinfunction "GND_6") (pintype "unspecified"))
      (node (ref "P3") (pin "2") (pinfunction "2_2") (pintype "unspecified"))
      (node (ref "P4") (pin "1") (pinfunction "1_1") (pintype "unspecified"))
      (node (ref "P4") (pin "4") (pinfunction "4_4") (pintype "unspecified"))
      (node (ref "P5") (pin "1") (pinfunction "1_1") (pintype "unspecified"))
      (node (ref "P6") (pin "1") (pintype "unspecified"))
      (node (ref "P9") (pin "1") (pintype "unspecified"))
      (node (ref "Q1") (pin "3") (pinfunction "E_3") (pintype "unspecified"))
      (node (ref "Q2") (pin "3") (pinfunction "E_3") (pintype "unspecified"))
      (node (ref "Q3") (pin "3") (pinfunction "E_3") (pintype "unspecified"))
      (node (ref "Q4") (pin "3") (pinfunction "E_3") (pintype "unspecified"))
      (node (ref "R14") (pin "2") (pinfunction "2_2") (pintype "unspecified"))
      (node (ref "R23") (pin "2") (pinfunction "2_2") (pintype "unspecified"))
      (node (ref "R24") (pin "1") (pinfunction "1_1") (pintype "unspecified"))
      (node (ref "R25") (pin "2") (pinfunction "2_2") (pintype "unspecified"))
      (node (ref "R26") (pin "1") (pinfunction "1_1") (pintype "unspecified"))
      (node (ref "R31") (pin "1") (pinfunction "A_1") (pintype "unspecified"))
      (node (ref "R32") (pin "1") (pinfunction "A_1") (pintype "unspecified"))
      (node (ref "R35") (pin "2") (pinfunction "2_2") (pintype "unspecified"))
      (node (ref "R36") (pin "2") (pinfunction "2_2") (pintype "unspecified"))
      (node (ref "R37") (pin "2") (pinfunction "2_2") (pintype "unspecified"))
      (node (ref "R38") (pin "2") (pinfunction "2_2") (pintype "unspecified"))
      (node (ref "R39") (pin "2") (pinfunction "2_2") (pintype "unspecified"))
      (node (ref "R40") (pin "2") (pinfunction "2_2") (pintype "unspecified"))
      (node (ref "R41") (pin "2") (pinfunction "2_2") (pintype "unspecified"))
      (node (ref "R42") (pin "2") (pinfunction "2_2") (pintype "unspecified"))
      (node (ref "R43") (pin "2") (pinfunction "2_2") (pintype "unspecified"))
      (node (ref "R44") (pin "2") (pinfunction "2_2") (pintype "unspecified"))
      (node (ref "R47") (pin "2") (pinfunction "2_2") (pintype "unspecified"))
      (node (ref "R48") (pin "2") (pinfunction "2_2") (pintype "input"))
      (node (ref "R6") (pin "1") (pinfunction "1_1") (pintype "unspecified"))
      (node (ref "R7") (pin "1") (pinfunction "1_1") (pintype "unspecified"))
      (node (ref "U10") (pin "5") (pinfunction "GND_5") (pintype "input"))
      (node (ref "U10") (pin "6") (pinfunction "GND_6") (pintype "input"))
      (node (ref "U10") (pin "7") (pinfunction "GND_7") (pintype "input"))
      (node (ref "U10") (pin "8") (pinfunction "GND_8") (pintype "input"))
      (node (ref "U2") (pin "1") (pinfunction "1_1") (pintype "unspecified"))
      (node (ref "U20") (pin "3") (pinfunction "GND_3") (pintype "unspecified"))
      (node (ref "U3") (pin "1") (pinfunction "GND_1") (pintype "unspecified"))
      (node (ref "U4") (pin "2") (pinfunction "2_2") (pintype "unspecified"))
      (node (ref "U5") (pin "23") (pinfunction "VSS_1_23") (pintype "unspecified"))
      (node (ref "U5") (pin "35") (pinfunction "VSS_2_35") (pintype "unspecified"))
      (node (ref "U5") (pin "47") (pinfunction "VSS_3_47") (pintype "unspecified"))
      (node (ref "U5") (pin "8") (pinfunction "VSSA_8") (pintype "unspecified"))
      (node (ref "U8") (pin "18") (pinfunction "GND_18") (pintype "unspecified"))
      (node (ref "U8") (pin "3") (pinfunction "GND_3") (pintype "unspecified"))
      (node (ref "U9") (pin "18") (pinfunction "GND_18") (pintype "unspecified"))
      (node (ref "U9") (pin "3") (pinfunction "GND_3") (pintype "unspecified"))
    )
    (net (code "13") (name "GYRO_RX") (class "Default")
      (node (ref "U5") (pin "22") (pinfunction "PB11_22") (pintype "bidirectional"))
    )
    (net (code "14") (name "GYRO_TX") (class "Default")
      (node (ref "U5") (pin "21") (pinfunction "PB10_21") (pintype "bidirectional"))
    )
    (net (code "15") (name "LASER_LOCATION") (class "Default")
      (node (ref "U5") (pin "19") (pinfunction "PB1_19") (pintype "bidirectional"))
    )
    (net (code "16") (name "LO") (class "Default")
      (node (ref "R11") (pin "2") (pinfunction "2_2") (pintype "unspecified"))
      (node (ref "U5") (pin "3") (pinfunction "PC14-OSC32_IN_3") (pintype "bidirectional"))
    )
    (net (code "17") (name "LO_OUT") (class "Default")
      (node (ref "F1") (pin "2") (pinfunction "2_2") (pintype "unspecified"))
      (node (ref "P1") (pin "1") (pinfunction "1_1") (pintype "unspecified"))
    )
    (net (code "18") (name "LX") (class "Default")
      (node (ref "P4") (pin "3") (pinfunction "3_3") (pintype "unspecified"))
      (node (ref "R17") (pin "2") (pinfunction "2_2") (pintype "unspecified"))
      (node (ref "R18") (pin "1") (pinfunction "1_1") (pintype "unspecified"))
    )
    (net (code "19") (name "LY") (class "Default")
      (node (ref "P4") (pin "2") (pinfunction "2_2") (pintype "unspecified"))
      (node (ref "R12") (pin "1") (pinfunction "1_1") (pintype "unspecified"))
      (node (ref "R13") (pin "1") (pinfunction "1_1") (pintype "unspecified"))
    )
    (net (code "20") (name "MOTOR_EN") (class "Default")
      (node (ref "R46") (pin "1") (pinfunction "1_1") (pintype "unspecified"))
      (node (ref "U5") (pin "16") (pinfunction "PA6_16") (pintype "bidirectional"))
      (node (ref "U8") (pin "2") (pinfunction "~ENABLE~_2") (pintype "unspecified"))
      (node (ref "U9") (pin "2") (pinfunction "~ENABLE~_2") (pintype "unspecified"))
    )
    (net (code "21") (name "MX_1A") (class "Default")
      (node (ref "P7") (pin "2") (pinfunction "2_2") (pintype "unspecified"))
      (node (ref "R38") (pin "1") (pinfunction "1_1") (pintype "unspecified"))
      (node (ref "U8") (pin "24") (pinfunction "OUT1A_24") (pintype "unspecified"))
    )
    (net (code "22") (name "MX_1B") (class "Default")
      (node (ref "P7") (pin "1") (pinfunction "1_1") (pintype "unspecified"))
      (node (ref "R37") (pin "1") (pinfunction "1_1") (pintype "unspecified"))
      (node (ref "U8") (pin "21") (pinfunction "OUT1B_21") (pintype "unspecified"))
    )
    (net (code "23") (name "MX_2A") (class "Default")
      (node (ref "P7") (pin "3") (pinfunction "3_3") (pintype "unspecified"))
      (node (ref "R39") (pin "1") (pinfunction "1_1") (pintype "unspecified"))
      (node (ref "U8") (pin "26") (pinfunction "OUT2A_26") (pintype "unspecified"))
    )
    (net (code "24") (name "MX_2B") (class "Default")
      (node (ref "P7") (pin "4") (pinfunction "4_4") (pintype "unspecified"))
      (node (ref "R40") (pin "1") (pinfunction "1_1") (pintype "unspecified"))
      (node (ref "U8") (pin "1") (pinfunction "OUT2B_1") (pintype "unspecified"))
    )
    (net (code "25") (name "MX_DIR") (class "Default")
      (node (ref "U5") (pin "13") (pinfunction "PA3_13") (pintype "bidirectional"))
      (node (ref "U8") (pin "19") (pinfunction "DIR_19") (pintype "unspecified"))
    )
    (net (code "26") (name "MX_STEP") (class "Default")
      (node (ref "U5") (pin "10") (pinfunction "PA0-WKUP_10") (pintype "bidirectional"))
      (node (ref "U8") (pin "16") (pinfunction "STEP_16") (pintype "unspecified"))
    )
    (net (code "27") (name "MY1_1A") (class "Default")
      (node (ref "P8") (pin "2") (pinfunction "2_2") (pintype "unspecified"))
      (node (ref "R42") (pin "1") (pinfunction "1_1") (pintype "unspecified"))
      (node (ref "U9") (pin "24") (pinfunction "OUT1A_24") (pintype "unspecified"))
    )
    (net (code "28") (name "MY1_1B") (class "Default")
      (node (ref "P8") (pin "1") (pinfunction "1_1") (pintype "unspecified"))
      (node (ref "R41") (pin "1") (pinfunction "1_1") (pintype "unspecified"))
      (node (ref "U9") (pin "21") (pinfunction "OUT1B_21") (pintype "unspecified"))
    )
    (net (code "29") (name "MY1_2A") (class "Default")
      (node (ref "P8") (pin "3") (pinfunction "3_3") (pintype "unspecified"))
      (node (ref "R43") (pin "1") (pinfunction "1_1") (pintype "unspecified"))
      (node (ref "U9") (pin "26") (pinfunction "OUT2A_26") (pintype "unspecified"))
    )
    (net (code "30") (name "MY1_2B") (class "Default")
      (node (ref "P8") (pin "4") (pinfunction "4_4") (pintype "unspecified"))
      (node (ref "R44") (pin "1") (pinfunction "1_1") (pintype "unspecified"))
      (node (ref "U9") (pin "1") (pinfunction "OUT2B_1") (pintype "unspecified"))
    )
    (net (code "31") (name "MY_DIR") (class "Default")
      (node (ref "U5") (pin "14") (pinfunction "PA4_14") (pintype "bidirectional"))
      (node (ref "U9") (pin "19") (pinfunction "DIR_19") (pintype "unspecified"))
    )
    (net (code "32") (name "MY_STEP") (class "Default")
      (node (ref "U5") (pin "11") (pinfunction "PA1_11") (pintype "bidirectional"))
      (node (ref "U9") (pin "16") (pinfunction "STEP_16") (pintype "unspecified"))
    )
    (net (code "33") (name "MZ_DIR") (class "Default")
      (node (ref "U5") (pin "15") (pinfunction "PA5_15") (pintype "bidirectional"))
    )
    (net (code "34") (name "MZ_STEP") (class "Default")
      (node (ref "U5") (pin "12") (pinfunction "PA2_12") (pintype "bidirectional"))
    )
    (net (code "35") (name "NRST") (class "Default")
      (node (ref "C15") (pin "2") (pinfunction "2_2") (pintype "unspecified"))
      (node (ref "R8") (pin "2") (pinfunction "2_2") (pintype "unspecified"))
      (node (ref "U5") (pin "7") (pinfunction "NRST_7") (pintype "bidirectional"))
    )
    (net (code "36") (name "Net-(C4-Pad1)") (class "Default")
      (node (ref "C4") (pin "1") (pinfunction "1_1") (pintype "unspecified"))
      (node (ref "U2") (pin "4") (pinfunction "4_4") (pintype "unspecified"))
    )
    (net (code "37") (name "Net-(C5-Pad1)") (class "Default")
      (node (ref "C5") (pin "1") (pinfunction "1_1") (pintype "unspecified"))
      (node (ref "U2") (pin "13") (pinfunction "13_13") (pintype "unspecified"))
    )
    (net (code "38") (name "Net-(C64-Pad2)") (class "Default")
      (node (ref "C64") (pin "2") (pinfunction "2_2") (pintype "input"))
      (node (ref "K1") (pin "3") (pinfunction "3_3") (pintype "unspecified"))
      (node (ref "K1") (pin "4") (pinfunction "4_4") (pintype "unspecified"))
      (node (ref "R85") (pin "2") (pinfunction "2_2") (pintype "input"))
      (node (ref "R86") (pin "1") (pinfunction "1_1") (pintype "input"))
    )
    (net (code "39") (name "Net-(D1-Pad2)") (class "Default")
      (node (ref "D1") (pin "2") (pinfunction "2_2") (pintype "unspecified"))
      (node (ref "H1") (pin "2") (pinfunction "2_2") (pintype "unspecified"))
    )
    (net (code "40") (name "Net-(D3-Pad1)") (class "Default")
      (node (ref "D3") (pin "1") (pinfunction "1_1") (pintype "unspecified"))
      (node (ref "R2") (pin "2") (pinfunction "2_2") (pintype "unspecified"))
    )
    (net (code "41") (name "Net-(D5-Pad2)") (class "Default")
      (node (ref "D5") (pin "2") (pinfunction "2_2") (pintype "unspecified"))
      (node (ref "R10") (pin "1") (pinfunction "1_1") (pintype "unspecified"))
    )
    (net (code "42") (name "Net-(D28-Pad1)") (class "Default")
      (node (ref "D28") (pin "1") (pinfunction "1_1") (pintype "unspecified"))
      (node (ref "K1") (pin "1") (pinfunction "1_1") (pintype "unspecified"))
      (node (ref "K1") (pin "2") (pinfunction "2_2") (pintype "unspecified"))
    )
    (net (code "43") (name "Net-(H2-Pad2)") (class "Default")
      (node (ref "H2") (pin "2") (pinfunction "2_2") (pintype "unspecified"))
      (node (ref "P3") (pin "1") (pinfunction "1_1") (pintype "unspecified"))
    )
    (net (code "44") (name "Net-(P4-Pad5)") (class "Default")
      (node (ref "P4") (pin "5") (pinfunction "5_5") (pintype "unspecified"))
      (node (ref "R93") (pin "1") (pinfunction "1_1") (pintype "unspecified"))
    )
    (net (code "45") (name "Net-(Q1-B)") (class "Default")
      (node (ref "Q1") (pin "1") (pinfunction "B_1") (pintype "unspecified"))
      (node (ref "R11") (pin "1") (pinfunction "1_1") (pintype "unspecified"))
      (node (ref "R14") (pin "1") (pinfunction "1_1") (pintype "unspecified"))
    )
    (net (code "46") (name "Net-(Q1-C)") (class "Default")
      (node (ref "F1") (pin "1") (pinfunction "1_1") (pintype "unspecified"))
      (node (ref "Q1") (pin "2") (pinfunction "C_2") (pintype "unspecified"))
      (node (ref "R10") (pin "2") (pinfunction "2_2") (pintype "unspecified"))
    )
    (net (code "47") (name "Net-(Q2-B)") (class "Default")
      (node (ref "Q2") (pin "1") (pinfunction "B_1") (pintype "unspecified"))
      (node (ref "R20") (pin "1") (pinfunction "1_1") (pintype "unspecified"))
    )
    (net (code "48") (name "Net-(Q2-C)") (class "Default")
      (node (ref "D8") (pin "2") (pinfunction "2_2") (pintype "unspecified"))
      (node (ref "P6") (pin "2") (pintype "unspecified"))
      (node (ref "Q2") (pin "2") (pinfunction "C_2") (pintype "unspecified"))
      (node (ref "R15") (pin "2") (pinfunction "2_2") (pintype "unspecified"))
    )
    (net (code "49") (name "Net-(Q3-B)") (class "Default")
      (node (ref "Q3") (pin "1") (pinfunction "B_1") (pintype "unspecified"))
      (node (ref "R87") (pin "1") (pinfunction "1_1") (pintype "unspecified"))
    )
    (net (code "50") (name "Net-(Q3-C)") (class "Default")
      (node (ref "D29") (pin "2") (pinfunction "2_2") (pintype "unspecified"))
      (node (ref "P9") (pin "2") (pintype "unspecified"))
      (node (ref "Q3") (pin "2") (pinfunction "C_2") (pintype "unspecified"))
      (node (ref "R88") (pin "2") (pinfunction "2_2") (pintype "unspecified"))
    )
    (net (code "51") (name "Net-(Q4-B)") (class "Default")
      (node (ref "Q4") (pin "1") (pinfunction "B_1") (pintype "unspecified"))
      (node (ref "R89") (pin "1") (pinfunction "1_1") (pintype "unspecified"))
    )
    (net (code "52") (name "Net-(Q4-C)") (class "Default")
      (node (ref "D30") (pin "2") (pinfunction "2_2") (pintype "unspecified"))
      (node (ref "P10") (pin "2") (pintype "unspecified"))
      (node (ref "Q4") (pin "2") (pinfunction "C_2") (pintype "unspecified"))
      (node (ref "R90") (pin "2") (pinfunction "2_2") (pintype "unspecified"))
    )
    (net (code "53") (name "Net-(R1-Pad1)") (class "Default")
      (node (ref "R1") (pin "1") (pinfunction "1_1") (pintype "unspecified"))
      (node (ref "U2") (pin "2") (pinfunction "2_2") (pintype "unspecified"))
    )
    (net (code "54") (name "Net-(R3-Pad1)") (class "Default")
      (node (ref "R3") (pin "1") (pinfunction "1_1") (pintype "unspecified"))
      (node (ref "U2") (pin "3") (pinfunction "3_3") (pintype "unspecified"))
    )
    (net (code "55") (name "Net-(R12-Pad2)") (class "Default")
      (node (ref "R12") (pin "2") (pinfunction "2_2") (pintype "unspecified"))
      (node (ref "R17") (pin "1") (pinfunction "1_1") (pintype "unspecified"))
      (node (ref "R91") (pin "1") (pinfunction "1_1") (pintype "unspecified"))
      (node (ref "R92") (pin "1") (pinfunction "1_1") (pintype "unspecified"))
    )
    (net (code "56") (name "Net-(R31-B)") (class "Default")
      (node (ref "R28") (pin "1") (pinfunction "1_1") (pintype "unspecified"))
      (node (ref "R31") (pin "3") (pinfunction "B_3") (pintype "unspecified"))
    )
    (net (code "57") (name "Net-(R31-TAP)") (class "Default")
      (node (ref "C32") (pin "1") (pinfunction "1_1") (pintype "unspecified"))
      (node (ref "R31") (pin "2") (pinfunction "TAP_2") (pintype "unspecified"))
      (node (ref "U8") (pin "17") (pinfunction "REF_17") (pintype "unspecified"))
    )
    (net (code "58") (name "Net-(R32-B)") (class "Default")
      (node (ref "R29") (pin "1") (pinfunction "1_1") (pintype "unspecified"))
      (node (ref "R32") (pin "3") (pinfunction "B_3") (pintype "unspecified"))
    )
    (net (code "59") (name "Net-(R32-TAP)") (class "Default")
      (node (ref "C33") (pin "1") (pinfunction "1_1") (pintype "unspecified"))
      (node (ref "R32") (pin "2") (pinfunction "TAP_2") (pintype "unspecified"))
      (node (ref "U9") (pin "17") (pinfunction "REF_17") (pintype "unspecified"))
    )
    (net (code "60") (name "Net-(U2-Pad5)") (class "Default")
      (node (ref "U2") (pin "5") (pinfunction "5_5") (pintype "unspecified"))
      (node (ref "U4") (pin "6") (pinfunction "6_6") (pintype "unspecified"))
    )
    (net (code "61") (name "Net-(U2-Pad6)") (class "Default")
      (node (ref "U2") (pin "6") (pinfunction "6_6") (pintype "unspecified"))
      (node (ref "U4") (pin "4") (pinfunction "4_4") (pintype "unspecified"))
    )
    (net (code "62") (name "Net-(U8-CP1)") (class "Default")
      (node (ref "C28") (pin "1") (pinfunction "1_1") (pintype "unspecified"))
      (node (ref "U8") (pin "4") (pinfunction "CP1_4") (pintype "unspecified"))
    )
    (net (code "63") (name "Net-(U8-CP2)") (class "Default")
      (node (ref "C28") (pin "2") (pinfunction "2_2") (pintype "unspecified"))
      (node (ref "U8") (pin "5") (pinfunction "CP2_5") (pintype "unspecified"))
    )
    (net (code "64") (name "Net-(U8-MS1)") (class "Default")
      (node (ref "R33") (pin "2") (pinfunction "2_2") (pintype "unspecified"))
      (node (ref "U8") (pin "10") (pinfunction "MS2_10") (pintype "unspecified"))
      (node (ref "U8") (pin "11") (pinfunction "MS3_11") (pintype "unspecified"))
      (node (ref "U8") (pin "12") (pinfunction "~RESET~_12") (pintype "unspecified"))
      (node (ref "U8") (pin "14") (pinfunction "~SLEEP~_14") (pintype "unspecified"))
      (node (ref "U8") (pin "9") (pinfunction "MS1_9") (pintype "unspecified"))
    )
    (net (code "65") (name "Net-(U8-SENSE1)") (class "Default")
      (node (ref "R24") (pin "2") (pinfunction "2_2") (pintype "unspecified"))
      (node (ref "U8") (pin "23") (pinfunction "SENSE1_23") (pintype "unspecified"))
    )
    (net (code "66") (name "Net-(U8-SENSE2)") (class "Default")
      (node (ref "R23") (pin "1") (pinfunction "1_1") (pintype "unspecified"))
      (node (ref "U8") (pin "27") (pinfunction "SENSE2_27") (pintype "unspecified"))
    )
    (net (code "67") (name "Net-(U8-VCP)") (class "Default")
      (node (ref "C30") (pin "1") (pinfunction "1_1") (pintype "unspecified"))
      (node (ref "U8") (pin "6") (pinfunction "VCP_6") (pintype "unspecified"))
    )
    (net (code "68") (name "Net-(U8-VREG)") (class "Default")
      (node (ref "C36") (pin "1") (pinfunction "1_1") (pintype "unspecified"))
      (node (ref "U8") (pin "8") (pinfunction "VREG_8") (pintype "unspecified"))
    )
    (net (code "69") (name "Net-(U8-~ROSC~)") (class "Default")
      (node (ref "R35") (pin "1") (pinfunction "1_1") (pintype "unspecified"))
      (node (ref "U8") (pin "13") (pinfunction "~ROSC~_13") (pintype "unspecified"))
    )
    (net (code "70") (name "Net-(U9-CP1)") (class "Default")
      (node (ref "C29") (pin "1") (pinfunction "1_1") (pintype "unspecified"))
      (node (ref "U9") (pin "4") (pinfunction "CP1_4") (pintype "unspecified"))
    )
    (net (code "71") (name "Net-(U9-CP2)") (class "Default")
      (node (ref "C29") (pin "2") (pinfunction "2_2") (pintype "unspecified"))
      (node (ref "U9") (pin "5") (pinfunction "CP2_5") (pintype "unspecified"))
    )
    (net (code "72") (name "Net-(U9-MS1)") (class "Default")
      (node (ref "R34") (pin "2") (pinfunction "2_2") (pintype "unspecified"))
      (node (ref "U9") (pin "10") (pinfunction "MS2_10") (pintype "unspecified"))
      (node (ref "U9") (pin "11") (pinfunction "MS3_11") (pintype "unspecified"))
      (node (ref "U9") (pin "12") (pinfunction "~RESET~_12") (pintype "unspecified"))
      (node (ref "U9") (pin "14") (pinfunction "~SLEEP~_14") (pintype "unspecified"))
      (node (ref "U9") (pin "9") (pinfunction "MS1_9") (pintype "unspecified"))
    )
    (net (code "73") (name "Net-(U9-SENSE1)") (class "Default")
      (node (ref "R26") (pin "2") (pinfunction "2_2") (pintype "unspecified"))
      (node (ref "U9") (pin "23") (pinfunction "SENSE1_23") (pintype "unspecified"))
    )
    (net (code "74") (name "Net-(U9-SENSE2)") (class "Default")
      (node (ref "R25") (pin "1") (pinfunction "1_1") (pintype "unspecified"))
      (node (ref "U9") (pin "27") (pinfunction "SENSE2_27") (pintype "unspecified"))
    )
    (net (code "75") (name "Net-(U9-VCP)") (class "Default")
      (node (ref "C31") (pin "1") (pinfunction "1_1") (pintype "unspecified"))
      (node (ref "U9") (pin "6") (pinfunction "VCP_6") (pintype "unspecified"))
    )
    (net (code "76") (name "Net-(U9-VREG)") (class "Default")
      (node (ref "C37") (pin "1") (pinfunction "1_1") (pintype "unspecified"))
      (node (ref "U9") (pin "8") (pinfunction "VREG_8") (pintype "unspecified"))
    )
    (net (code "77") (name "Net-(U9-~ROSC~)") (class "Default")
      (node (ref "R36") (pin "1") (pinfunction "1_1") (pintype "unspecified"))
      (node (ref "U9") (pin "13") (pinfunction "~ROSC~_13") (pintype "unspecified"))
    )
    (net (code "78") (name "Net-(U10-ON{slash}OFF)") (class "Default")
      (node (ref "R47") (pin "1") (pinfunction "1_1") (pintype "unspecified"))
      (node (ref "U10") (pin "4") (pinfunction "ON/OFF_4") (pintype "input"))
    )
    (net (code "79") (name "Net-(U10-OUTPUT)") (class "Default")
      (node (ref "D27") (pin "2") (pinfunction "2_2") (pintype "input"))
      (node (ref "L3") (pin "2") (pinfunction "2_2") (pintype "unspecified"))
      (node (ref "U10") (pin "2") (pinfunction "OUTPUT_2") (pintype "input"))
    )
    (net (code "80") (name "Net-(U20-Y)") (class "Default")
      (node (ref "R9") (pin "2") (pinfunction "2_2") (pintype "unspecified"))
      (node (ref "U20") (pin "4") (pinfunction "Y_4") (pintype "unspecified"))
    )
    (net (code "81") (name "Net-(Y1-OSC1)") (class "Default")
      (node (ref "C13") (pin "1") (pinfunction "1_1") (pintype "unspecified"))
      (node (ref "U2") (pin "8") (pinfunction "8_8") (pintype "unspecified"))
      (node (ref "Y1") (pin "1") (pinfunction "OSC1_1") (pintype "unspecified"))
    )
    (net (code "82") (name "Net-(Y1-OSC2)") (class "Default")
      (node (ref "C11") (pin "1") (pinfunction "1_1") (pintype "unspecified"))
      (node (ref "U2") (pin "7") (pinfunction "7_7") (pintype "unspecified"))
      (node (ref "Y1") (pin "2") (pinfunction "OSC2_2") (pintype "unspecified"))
    )
    (net (code "83") (name "PROBE") (class "Default")
      (node (ref "U5") (pin "38") (pinfunction "PA15/JTDI_38") (pintype "bidirectional"))
    )
    (net (code "84") (name "PWM_5V") (class "Default")
      (node (ref "P3") (pin "3") (pinfunction "3_3") (pintype "unspecified"))
      (node (ref "R9") (pin "1") (pinfunction "1_1") (pintype "unspecified"))
    )
    (net (code "85") (name "RST") (class "Default")
      (node (ref "C5") (pin "2") (pinfunction "2_2") (pintype "unspecified"))
      (node (ref "R85") (pin "1") (pinfunction "1_1") (pintype "input"))
      (node (ref "U5") (pin "41") (pinfunction "PB5_41") (pintype "bidirectional"))
    )
    (net (code "86") (name "RXD") (class "Default")
      (node (ref "R1") (pin "2") (pinfunction "2_2") (pintype "unspecified"))
      (node (ref "R27") (pin "2") (pinfunction "2_2") (pintype "unspecified"))
      (node (ref "U5") (pin "31") (pinfunction "PA10_31") (pintype "bidirectional"))
    )
    (net (code "87") (name "SAFETY_DOOR") (class "Default")
      (node (ref "U5") (pin "45") (pinfunction "PB8_45") (pintype "bidirectional"))
    )
    (net (code "88") (name "SPINDLE_DIR") (class "Default")
      (node (ref "U5") (pin "27") (pinfunction "PB14_27") (pintype "bidirectional"))
    )
    (net (code "89") (name "SPINDLE_EN") (class "Default")
      (node (ref "U5") (pin "26") (pinfunction "PB13_26") (pintype "bidirectional"))
    )
    (net (code "90") (name "SPINDLE_PWM") (class "Default")
      (node (ref "R48") (pin "1") (pinfunction "1_1") (pintype "input"))
      (node (ref "U20") (pin "2") (pinfunction "A_2") (pintype "unspecified"))
      (node (ref "U5") (pin "29") (pinfunction "PA8_29") (pintype "bidirectional"))
    )
    (net (code "91") (name "SWCLK") (class "Default")
      (node (ref "P5") (pin "3") (pinfunction "3_3") (pintype "unspecified"))
      (node (ref "U5") (pin "37") (pinfunction "PA14/JTCK/SWCLK_37") (pintype "bidirectional"))
    )
    (net (code "92") (name "SWDIO") (class "Default")
      (node (ref "P5") (pin "4") (pinfunction "4_4") (pintype "unspecified"))
      (node (ref "U5") (pin "34") (pinfunction "PA13/JTMS/SWDIO_34") (pintype "bidirectional"))
    )
    (net (code "93") (name "TXD") (class "Default")
      (node (ref "R3") (pin "2") (pinfunction "2_2") (pintype "unspecified"))
      (node (ref "R30") (pin "2") (pinfunction "2_2") (pintype "unspecified"))
      (node (ref "U5") (pin "30") (pinfunction "PA9_30") (pintype "bidirectional"))
    )
    (net (code "94") (name "USBV_CK") (class "Default")
      (node (ref "U5") (pin "18") (pinfunction "PB0_18") (pintype "bidirectional"))
    )
    (net (code "95") (name "USB_DM") (class "Default")
      (node (ref "P2") (pin "2") (pinfunction "D-_2") (pintype "unspecified"))
      (node (ref "U4") (pin "3") (pinfunction "3_3") (pintype "unspecified"))
    )
    (net (code "96") (name "USB_DP") (class "Default")
      (node (ref "P2") (pin "3") (pinfunction "D+_3") (pintype "unspecified"))
      (node (ref "U4") (pin "1") (pinfunction "1_1") (pintype "unspecified"))
    )
    (net (code "97") (name "VCC") (class "Default")
      (node (ref "C12") (pin "2") (pinfunction "2_2") (pintype "unspecified"))
      (node (ref "C3") (pin "1") (pinfunction "1_1") (pintype "unspecified"))
      (node (ref "C34") (pin "1") (pinfunction "1_1") (pintype "unspecified"))
      (node (ref "C35") (pin "1") (pinfunction "1_1") (pintype "unspecified"))
      (node (ref "C42") (pin "1") (pinfunction "1_1") (pintype "input"))
      (node (ref "C69") (pin "1") (pinfunction "1_1") (pintype "input"))
      (node (ref "C70") (pin "1") (pinfunction "1_1") (pintype "input"))
      (node (ref "D32") (pin "2") (pinfunction "2_2") (pintype "input"))
      (node (ref "D5") (pin "1") (pinfunction "1_1") (pintype "unspecified"))
      (node (ref "H1") (pin "1") (pinfunction "1_1") (pintype "unspecified"))
      (node (ref "L3") (pin "1") (pinfunction "1_1") (pintype "unspecified"))
      (node (ref "R15") (pin "1") (pinfunction "1_1") (pintype "unspecified"))
      (node (ref "R28") (pin "2") (pinfunction "2_2") (pintype "unspecified"))
      (node (ref "R29") (pin "2") (pinfunction "2_2") (pintype "unspecified"))
      (node (ref "R33") (pin "1") (pinfunction "1_1") (pintype "unspecified"))
      (node (ref "R34") (pin "1") (pinfunction "1_1") (pintype "unspecified"))
      (node (ref "R88") (pin "1") (pinfunction "1_1") (pintype "unspecified"))
      (node (ref "R90") (pin "1") (pinfunction "1_1") (pintype "unspecified"))
      (node (ref "R91") (pin "2") (pinfunction "2_2") (pintype "unspecified"))
      (node (ref "R93") (pin "2") (pinfunction "2_2") (pintype "unspecified"))
      (node (ref "U10") (pin "3") (pinfunction "FB_3") (pintype "input"))
      (node (ref "U2") (pin "16") (pinfunction "16_16") (pintype "unspecified"))
      (node (ref "U20") (pin "5") (pinfunction "VCC_5") (pintype "unspecified"))
      (node (ref "U3") (pin "3") (pinfunction "IN_3") (pintype "unspecified"))
      (node (ref "U8") (pin "15") (pinfunction "VDD_15") (pintype "unspecified"))
      (node (ref "U9") (pin "15") (pinfunction "VDD_15") (pintype "unspecified"))
    )
    (net (code "98") (name "VM") (class "Default")
      (node (ref "C2") (pin "1") (pintype "unspecified"))
      (node (ref "C30") (pin "2") (pinfunction "2_2") (pintype "unspecified"))
      (node (ref "C31") (pin "2") (pinfunction "2_2") (pintype "unspecified"))
      (node (ref "C44") (pin "1") (pinfunction "1_1") (pintype "input"))
      (node (ref "C45") (pin "1") (pinfunction "1_1") (pintype "input"))
      (node (ref "C46") (pin "1") (pinfunction "1_1") (pintype "input"))
      (node (ref "C47") (pin "1") (pinfunction "1_1") (pintype "input"))
      (node (ref "C65") (pin "1") (pinfunction "1_1") (pintype "unspecified"))
      (node (ref "D2") (pin "1") (pinfunction "1_1") (pintype "unspecified"))
      (node (ref "DZ3") (pin "2") (pinfunction "2_2") (pintype "unspecified"))
      (node (ref "P1") (pin "4") (pinfunction "4_4") (pintype "unspecified"))
      (node (ref "U8") (pin "22") (pinfunction "VBB1_22") (pintype "unspecified"))
      (node (ref "U8") (pin "28") (pinfunction "VBB2_28") (pintype "unspecified"))
      (node (ref "U9") (pin "22") (pinfunction "VBB1_22") (pintype "unspecified"))
      (node (ref "U9") (pin "28") (pinfunction "VBB2_28") (pintype "unspecified"))
    )
    (net (code "99") (name "VUSB") (class "Default")
      (node (ref "D1") (pin "1") (pinfunction "1_1") (pintype "unspecified"))
      (node (ref "P2") (pin "1") (pinfunction "VBUS_1") (pintype "unspecified"))
      (node (ref "U4") (pin "5") (pinfunction "5_5") (pintype "unspecified"))
    )
    (net (code "100") (name "XTAL1") (class "Default")
      (node (ref "C17") (pin "1") (pinfunction "1_1") (pintype "unspecified"))
      (node (ref "U5") (pin "5") (pinfunction "OSC_IN/PD0_5") (pintype "input"))
      (node (ref "Y2") (pin "1") (pinfunction "OSC1_1") (pintype "unspecified"))
    )
    (net (code "101") (name "XTAL2") (class "Default")
      (node (ref "C16") (pin "1") (pinfunction "1_1") (pintype "unspecified"))
      (node (ref "U5") (pin "6") (pinfunction "OSC_OUT/PD1_6") (pintype "output"))
      (node (ref "Y2") (pin "2") (pinfunction "OSC2_2") (pintype "unspecified"))
    )
    (net (code "102") (name "X_LIMT") (class "Default")
      (node (ref "C19") (pin "2") (pinfunction "2_2") (pintype "unspecified"))
      (node (ref "R18") (pin "2") (pinfunction "2_2") (pintype "unspecified"))
      (node (ref "U5") (pin "25") (pinfunction "PB12_25") (pintype "bidirectional"))
    )
    (net (code "103") (name "Y_LIMT") (class "Default")
      (node (ref "C18") (pin "2") (pinfunction "2_2") (pintype "unspecified"))
      (node (ref "R13") (pin "2") (pinfunction "2_2") (pintype "unspecified"))
      (node (ref "U5") (pin "28") (pinfunction "PB15_28") (pintype "bidirectional"))
    )
    (net (code "104") (name "unconnected-(U2-Pad9)") (class "Default")
      (node (ref "U2") (pin "9") (pinfunction "9_9") (pintype "unspecified"))
    )
    (net (code "105") (name "unconnected-(U2-Pad10)") (class "Default")
      (node (ref "U2") (pin "10") (pinfunction "10_10") (pintype "unspecified"))
    )
    (net (code "106") (name "unconnected-(U2-Pad11)") (class "Default")
      (node (ref "U2") (pin "11") (pinfunction "11_11") (pintype "unspecified"))
    )
    (net (code "107") (name "unconnected-(U2-Pad12)") (class "Default")
      (node (ref "U2") (pin "12") (pinfunction "12_12") (pintype "unspecified"))
    )
    (net (code "108") (name "unconnected-(U2-Pad14)") (class "Default")
      (node (ref "U2") (pin "14") (pinfunction "14_14") (pintype "unspecified"))
    )
    (net (code "109") (name "unconnected-(U2-Pad15)") (class "Default")
      (node (ref "U2") (pin "15") (pinfunction "15_15") (pintype "unspecified"))
    )
    (net (code "110") (name "unconnected-(U5-PA11-Pad32)") (class "Default")
      (node (ref "U5") (pin "32") (pinfunction "PA11_32") (pintype "bidirectional"))
    )
    (net (code "111") (name "unconnected-(U5-PA12-Pad33)") (class "Default")
      (node (ref "U5") (pin "33") (pinfunction "PA12_33") (pintype "bidirectional"))
    )
    (net (code "112") (name "unconnected-(U5-PB9-Pad46)") (class "Default")
      (node (ref "U5") (pin "46") (pinfunction "PB9_46") (pintype "bidirectional"))
    )
    (net (code "113") (name "unconnected-(U5-PC13-TAMPER-RTC-Pad2)") (class "Default")
      (node (ref "U5") (pin "2") (pinfunction "PC13-TAMPER-RTC_2") (pintype "bidirectional"))
    )
    (net (code "114") (name "unconnected-(U5-VBAT-Pad1)") (class "Default")
      (node (ref "U5") (pin "1") (pinfunction "VBAT_1") (pintype "unspecified"))
    )
    (net (code "115") (name "unconnected-(U8-NC-Pad7)") (class "Default")
      (node (ref "U8") (pin "7") (pinfunction "NC_7") (pintype "unspecified"))
    )
    (net (code "116") (name "unconnected-(U8-NC-Pad20)") (class "Default")
      (node (ref "U8") (pin "20") (pinfunction "NC_20") (pintype "unspecified"))
    )
    (net (code "117") (name "unconnected-(U8-NC-Pad25)") (class "Default")
      (node (ref "U8") (pin "25") (pinfunction "NC_25") (pintype "unspecified"))
    )
    (net (code "118") (name "unconnected-(U9-NC-Pad7)") (class "Default")
      (node (ref "U9") (pin "7") (pinfunction "NC_7") (pintype "unspecified"))
    )
    (net (code "119") (name "unconnected-(U9-NC-Pad20)") (class "Default")
      (node (ref "U9") (pin "20") (pinfunction "NC_20") (pintype "unspecified"))
    )
    (net (code "120") (name "unconnected-(U9-NC-Pad25)") (class "Default")
      (node (ref "U9") (pin "25") (pinfunction "NC_25") (pintype "unspecified"))
    )
    (net (code "121") (name "unconnected-(U20-NC-Pad1)") (class "Default")
      (node (ref "U20") (pin "1") (pinfunction "NC_1") (pintype "unspecified"))
    )
  )
)
